# 11-ANALOG.net
KiCad netlist of a schematic drawn in Altium Designer
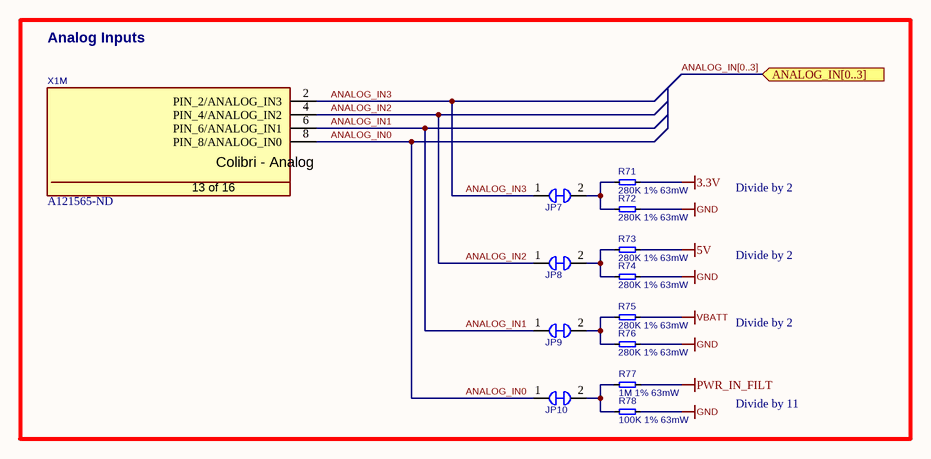
[diagram p0: 11-ANALOG.SchDoc]

(export (version "E")
  (design (tool "Eeschema 10.0.6"))
  (components
    (comp (ref "JP7")
      (value "Jumper NC SMD")
      (footprint "NC")
      (description "SMD jumper normally closed")
      (libsource (lib "Connectors") (part "Jumper NC SMD"))
    )
    (comp (ref "JP8")
      (value "Jumper NC SMD")
      (footprint "NC")
      (description "SMD jumper normally closed")
      (libsource (lib "Connectors") (part "Jumper NC SMD"))
    )
    (comp (ref "JP9")
      (value "Jumper NC SMD")
      (footprint "NC")
      (description "SMD jumper normally closed")
      (libsource (lib "Connectors") (part "Jumper NC SMD"))
    )
    (comp (ref "JP10")
      (value "Jumper NC SMD")
      (footprint "NC")
      (description "SMD jumper normally closed")
      (libsource (lib "Connectors") (part "Jumper NC SMD"))
    )
    (comp (ref "R71")
      (value "280K 1% 63mW")
      (footprint "RESC1005X40N")
      (description "Resistor 280Kohm 63mW 1% 0402")
      (fields (field (name "POWER") "63mW") (field (name "TOLERANCE") "1%"))
      (libsource (lib "AI Gateway - Carrier") (part "R-280K-1%-0402"))
    )
    (comp (ref "R72")
      (value "280K 1% 63mW")
      (footprint "RESC1005X40N")
      (description "Resistor 280Kohm 63mW 1% 0402")
      (fields (field (name "POWER") "63mW") (field (name "TOLERANCE") "1%"))
      (libsource (lib "AI Gateway - Carrier") (part "R-280K-1%-0402"))
    )
    (comp (ref "R73")
      (value "280K 1% 63mW")
      (footprint "RESC1005X40N")
      (description "Resistor 280Kohm 63mW 1% 0402")
      (fields (field (name "POWER") "63mW") (field (name "TOLERANCE") "1%"))
      (libsource (lib "AI Gateway - Carrier") (part "R-280K-1%-0402"))
    )
    (comp (ref "R74")
      (value "280K 1% 63mW")
      (footprint "RESC1005X40N")
      (description "Resistor 280Kohm 63mW 1% 0402")
      (fields (field (name "POWER") "63mW") (field (name "TOLERANCE") "1%"))
      (libsource (lib "AI Gateway - Carrier") (part "R-280K-1%-0402"))
    )
    (comp (ref "R75")
      (value "280K 1% 63mW")
      (footprint "RESC1005X40N")
      (description "Resistor 280Kohm 63mW 1% 0402")
      (fields (field (name "POWER") "63mW") (field (name "TOLERANCE") "1%"))
      (libsource (lib "AI Gateway - Carrier") (part "R-280K-1%-0402"))
    )
    (comp (ref "R76")
      (value "280K 1% 63mW")
      (footprint "RESC1005X40N")
      (description "Resistor 280Kohm 63mW 1% 0402")
      (fields (field (name "POWER") "63mW") (field (name "TOLERANCE") "1%"))
      (libsource (lib "AI Gateway - Carrier") (part "R-280K-1%-0402"))
    )
    (comp (ref "R77")
      (value "1M 1% 63mW")
      (footprint "RESC1005X40N")
      (description "Resistor 1Mohm 63mW 1% 0402")
      (fields (field (name "POWER") "63mW") (field (name "TOLERANCE") "1%"))
      (libsource (lib "AI Gateway - Carrier") (part "R-1M-1%-0402"))
    )
    (comp (ref "R78")
      (value "100K 1% 63mW")
      (footprint "RESC1005X40N")
      (description "Resistor 100Kohm 63mW 1% 0402")
      (fields (field (name "POWER") "63mW") (field (name "TOLERANCE") "1%"))
      (libsource (lib "AI Gateway - Carrier") (part "R-100K-1%-0402"))
    )
    (comp (ref "X1")
      (value "1473005-1")
      (footprint "T_Tyco_1473005-1")
      (description "SODIMM Connector")
      (fields (field (name "SUPPLIER PART NUMBER 1") "A121565-ND"))
      (libsource (lib "Connectors") (part "CON-Tyco-1473005-1-200-0.6mm"))
    )
  )
  (nets
    (net (code "1") (name "/ANALOG_IN0") (class "Default")
      (node (ref "JP10") (pin "1") (pinfunction "1_1") (pintype "passive"))
      (node (ref "X1") (pin "8") (pinfunction "PIN_8/ANALOG_IN0_8") (pintype "passive"))
    )
    (net (code "2") (name "/ANALOG_IN1") (class "Default")
      (node (ref "JP9") (pin "1") (pinfunction "1_1") (pintype "passive"))
      (node (ref "X1") (pin "6") (pinfunction "PIN_6/ANALOG_IN1_6") (pintype "passive"))
    )
    (net (code "3") (name "/ANALOG_IN2") (class "Default")
      (node (ref "JP8") (pin "1") (pinfunction "1_1") (pintype "passive"))
      (node (ref "X1") (pin "4") (pinfunction "PIN_4/ANALOG_IN2_4") (pintype "passive"))
    )
    (net (code "4") (name "/ANALOG_IN3") (class "Default")
      (node (ref "JP7") (pin "1") (pinfunction "1_1") (pintype "passive"))
      (node (ref "X1") (pin "2") (pinfunction "PIN_2/ANALOG_IN3_2") (pintype "passive"))
    )
    (net (code "6") (name "3.3V") (class "Default")
      (node (ref "R71") (pin "2") (pinfunction "2_2") (pintype "passive"))
    )
    (net (code "7") (name "5V") (class "Default")
      (node (ref "R73") (pin "2") (pinfunction "2_2") (pintype "passive"))
    )
    (net (code "8") (name "GND") (class "Default")
      (node (ref "R72") (pin "2") (pinfunction "2_2") (pintype "passive"))
      (node (ref "R74") (pin "2") (pinfunction "2_2") (pintype "passive"))
      (node (ref "R76") (pin "2") (pinfunction "2_2") (pintype "passive"))
      (node (ref "R78") (pin "1") (pinfunction "1_1") (pintype "passive"))
    )
    (net (code "9") (name "Net-(JP7-Pad2)") (class "Default")
      (node (ref "JP7") (pin "2") (pinfunction "2_2") (pintype "passive"))
      (node (ref "R71") (pin "1") (pinfunction "1_1") (pintype "passive"))
      (node (ref "R72") (pin "1") (pinfunction "1_1") (pintype "passive"))
    )
    (net (code "10") (name "Net-(JP8-Pad2)") (class "Default")
      (node (ref "JP8") (pin "2") (pinfunction "2_2") (pintype "passive"))
      (node (ref "R73") (pin "1") (pinfunction "1_1") (pintype "passive"))
      (node (ref "R74") (pin "1") (pinfunction "1_1") (pintype "passive"))
    )
    (net (code "11") (name "Net-(JP9-Pad2)") (class "Default")
      (node (ref "JP9") (pin "2") (pinfunction "2_2") (pintype "passive"))
      (node (ref "R75") (pin "1") (pinfunction "1_1") (pintype "passive"))
      (node (ref "R76") (pin "1") (pinfunction "1_1") (pintype "passive"))
    )
    (net (code "12") (name "Net-(JP10-Pad2)") (class "Default")
      (node (ref "JP10") (pin "2") (pinfunction "2_2") (pintype "passive"))
      (node (ref "R77") (pin "2") (pinfunction "2_2") (pintype "passive"))
      (node (ref "R78") (pin "2") (pinfunction "2_2") (pintype "passive"))
    )
    (net (code "13") (name "PWR_IN_FILT") (class "Default")
      (node (ref "R77") (pin "1") (pinfunction "1_1") (pintype "passive"))
    )
    (net (code "14") (name "VBATT") (class "Default")
      (node (ref "R75") (pin "2") (pinfunction "2_2") (pintype "passive"))
    )
  )
)
